# Hexagon_Robot1.net
KiCad netlist of a schematic drawn in EasyEDA
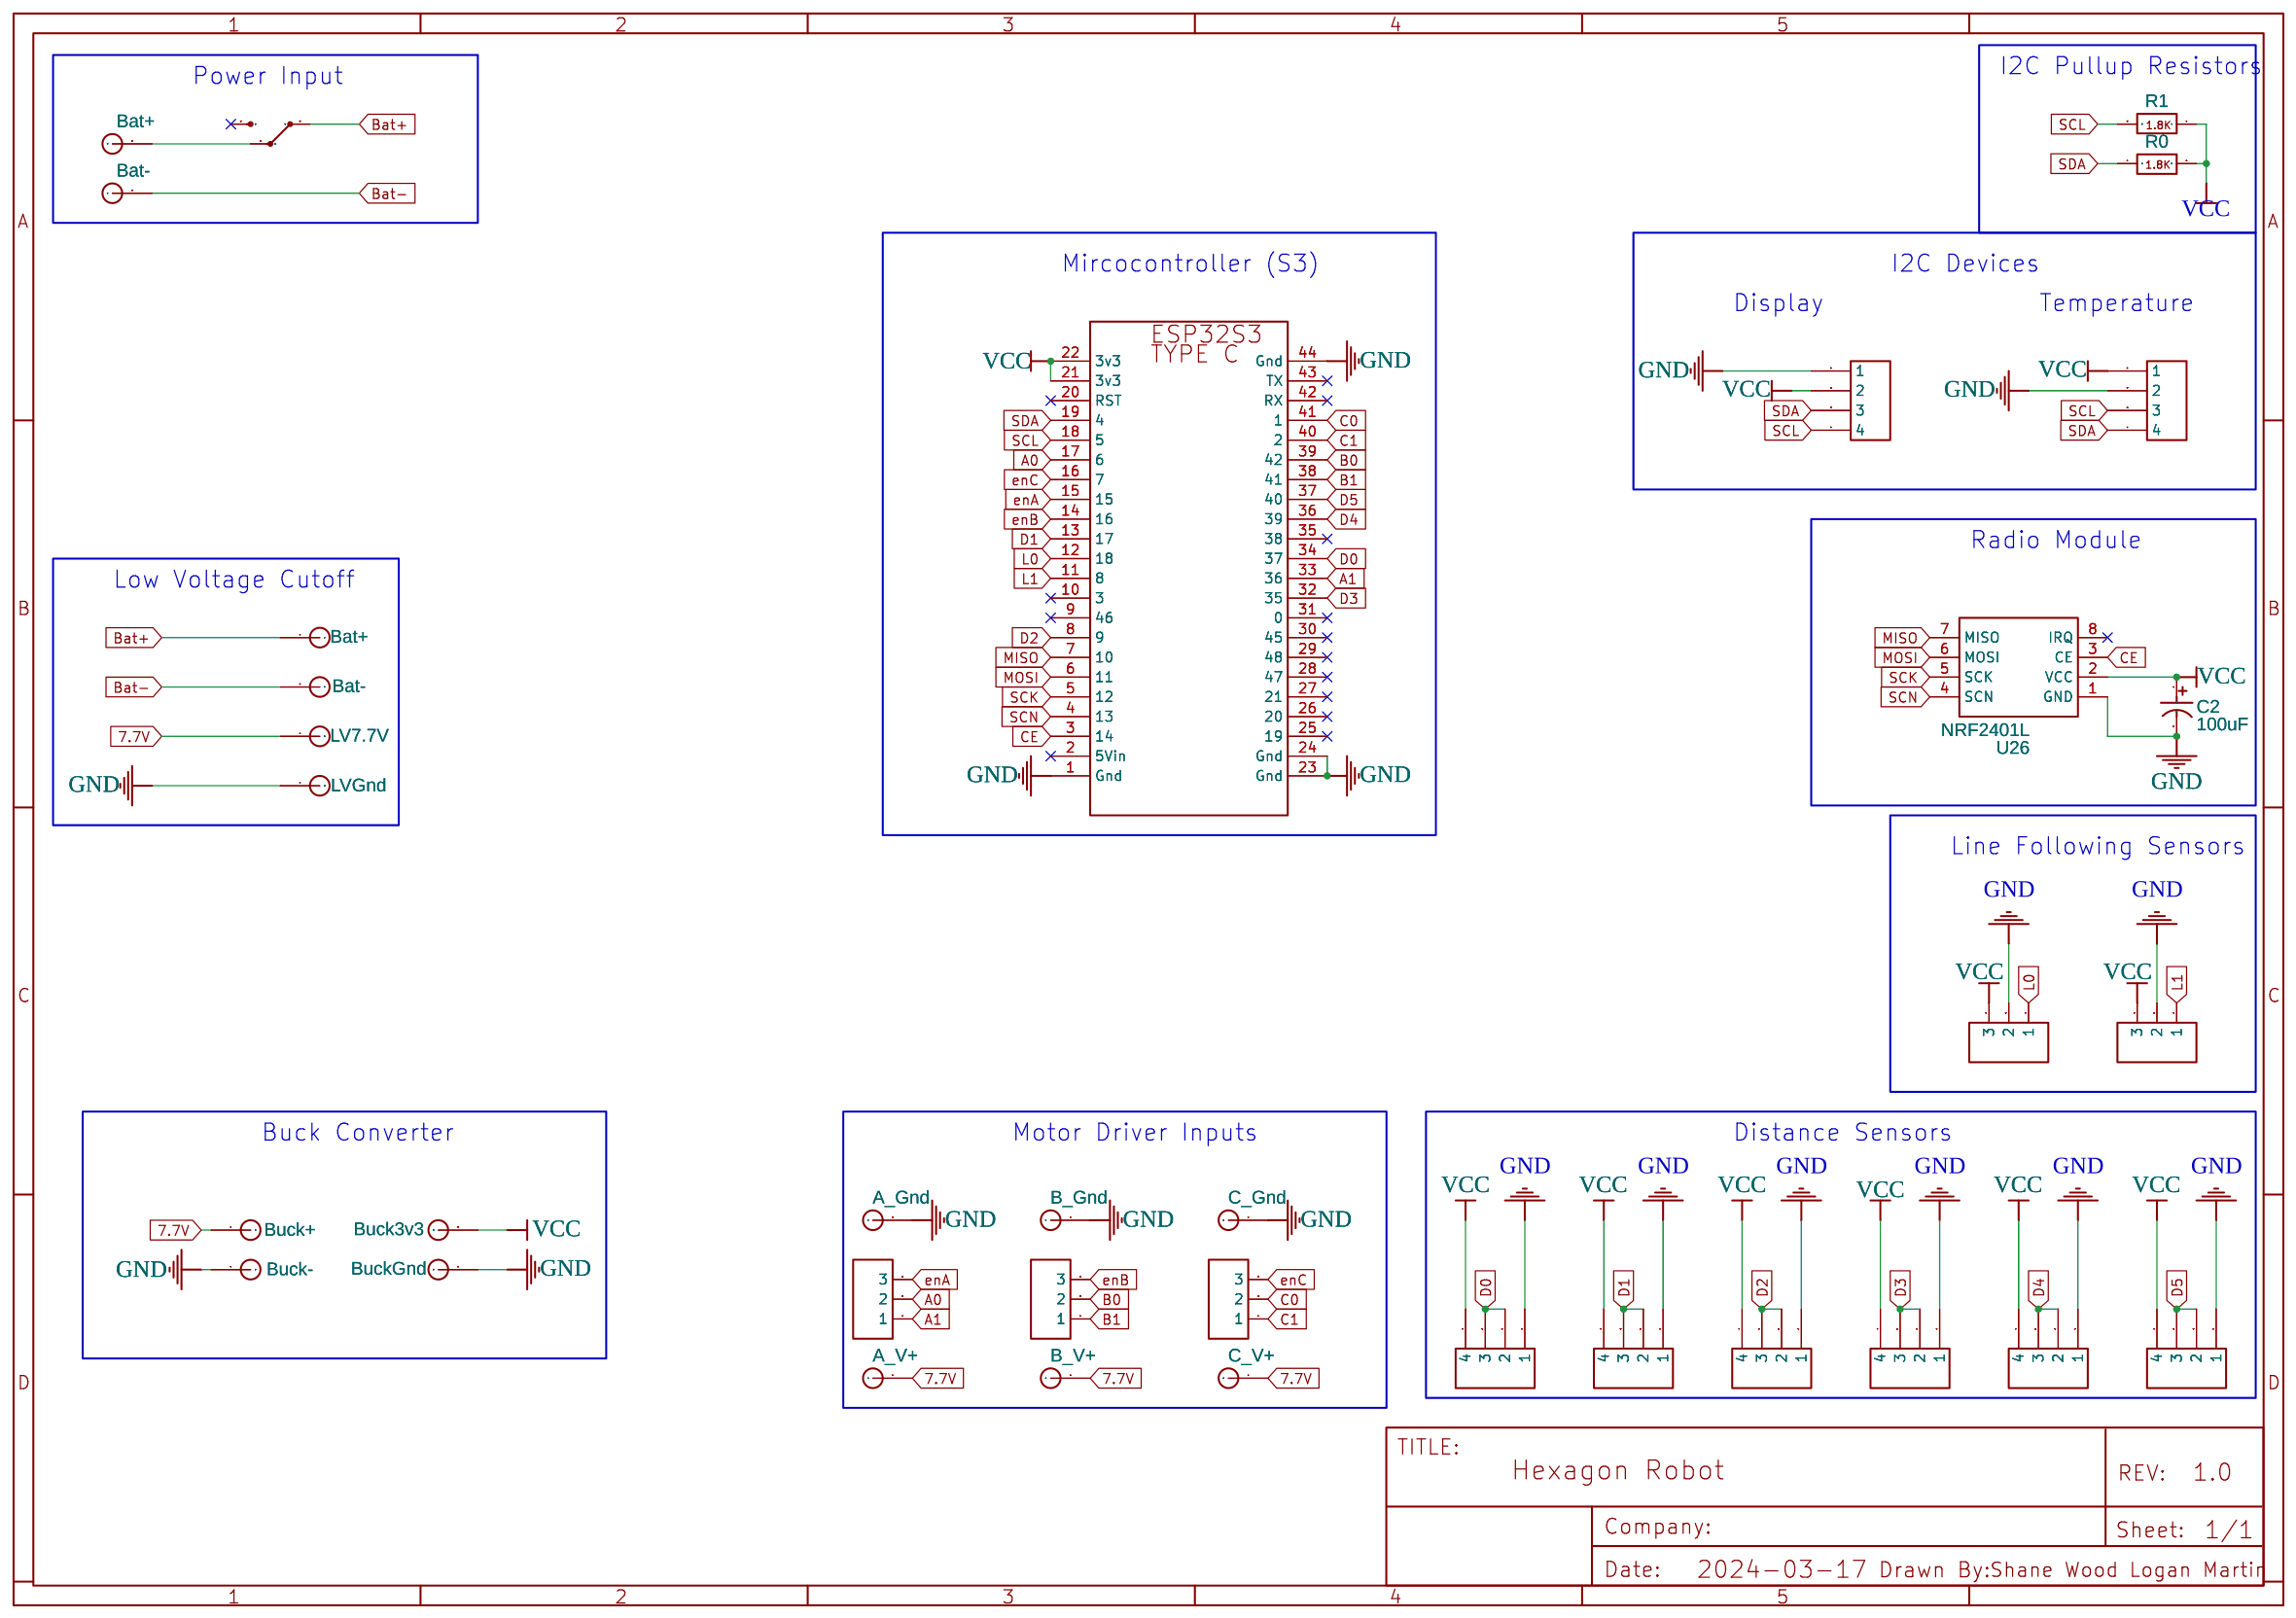
[diagram p0: schematic sheet]

(export (version "E")
  (design (tool "Eeschema 10.0.6"))
  (components
    (comp (ref "C2")
      (value "100uF")
      (fields (field (name "Manufacturer Part") "Jweo"))
      (libsource (lib "") (part "CAP-POL-1"))
    )
    (comp (ref "H1")
      (value "Bat+")
      (fields (field (name "Manufacturer Part") "Wire Hole"))
      (libsource (lib "") (part "Wire Hole 14AWG_1"))
    )
    (comp (ref "H2")
      (value "Bat-")
      (fields (field (name "Manufacturer Part") "Wire Hole"))
      (libsource (lib "") (part "Wire Hole 14AWG_1"))
    )
    (comp (ref "H3")
      (value "Bat+")
      (fields (field (name "Manufacturer Part") "Wire Hole"))
      (libsource (lib "") (part "Wire Hole 14AWG"))
    )
    (comp (ref "H4")
      (value "LVGnd")
      (fields (field (name "Manufacturer Part") "Wire Hole"))
      (libsource (lib "") (part "Wire Hole 14AWG"))
    )
    (comp (ref "H5")
      (value "Bat-")
      (fields (field (name "Manufacturer Part") "Wire Hole"))
      (libsource (lib "") (part "Wire Hole 14AWG"))
    )
    (comp (ref "H6")
      (value "LV7.7V")
      (fields (field (name "Manufacturer Part") "Wire Hole"))
      (libsource (lib "") (part "Wire Hole 14AWG"))
    )
    (comp (ref "H11")
      (value "A_Gnd")
      (fields (field (name "Manufacturer Part") "Wire Hole"))
      (libsource (lib "") (part "Wire Hole 14AWG_1"))
    )
    (comp (ref "H12")
      (value "B_Gnd")
      (fields (field (name "Manufacturer Part") "Wire Hole"))
      (libsource (lib "") (part "Wire Hole 14AWG_1"))
    )
    (comp (ref "H13")
      (value "C_Gnd")
      (fields (field (name "Manufacturer Part") "Wire Hole"))
      (libsource (lib "") (part "Wire Hole 14AWG_1"))
    )
    (comp (ref "H14")
      (value "A_V+")
      (fields (field (name "Manufacturer Part") "Wire Hole"))
      (libsource (lib "") (part "Wire Hole 14AWG_1"))
    )
    (comp (ref "H15")
      (value "B_V+")
      (fields (field (name "Manufacturer Part") "Wire Hole"))
      (libsource (lib "") (part "Wire Hole 14AWG_1"))
    )
    (comp (ref "H16")
      (value "C_V+")
      (fields (field (name "Manufacturer Part") "Wire Hole"))
      (libsource (lib "") (part "Wire Hole 14AWG_1"))
    )
    (comp (ref "H17")
      (value "Buck+")
      (fields (field (name "Manufacturer Part") "Wire Hole"))
      (libsource (lib "") (part "Wire Hole 14AWG"))
    )
    (comp (ref "H18")
      (value "Buck-")
      (fields (field (name "Manufacturer Part") "Wire Hole"))
      (libsource (lib "") (part "Wire Hole 14AWG"))
    )
    (comp (ref "H19")
      (value "Buck3v3")
      (fields (field (name "Manufacturer Part") "Wire Hole"))
      (libsource (lib "") (part "Wire Hole 14AWG_1"))
    )
    (comp (ref "H20")
      (value "BuckGnd")
      (fields (field (name "Manufacturer Part") "Wire Hole"))
      (libsource (lib "") (part "Wire Hole 14AWG_1"))
    )
    (comp (ref "P9")
      (value "Header-Female-2.54_1x3")
      (fields
        (field (name "Manufacturer Part") "Header-Female-2.54_1x4")
        (field (name "Manufacturer") "ReliaPro")
      )
      (libsource (lib "") (part "Header-Female-2.54_1x3_1"))
    )
    (comp (ref "P10")
      (value "Header-Female-2.54_1x3")
      (fields
        (field (name "Manufacturer Part") "Header-Female-2.54_1x4")
        (field (name "Manufacturer") "ReliaPro")
      )
      (libsource (lib "") (part "Header-Female-2.54_1x3_1"))
    )
    (comp (ref "P11")
      (value "Header-Female-2.54_1x3")
      (fields
        (field (name "Manufacturer Part") "Header-Female-2.54_1x4")
        (field (name "Manufacturer") "ReliaPro")
      )
      (libsource (lib "") (part "Header-Female-2.54_1x3"))
    )
    (comp (ref "P12")
      (value "Header-Female-2.54_1x3")
      (fields
        (field (name "Manufacturer Part") "Header-Female-2.54_1x4")
        (field (name "Manufacturer") "ReliaPro")
      )
      (libsource (lib "") (part "Header-Female-2.54_1x3"))
    )
    (comp (ref "P13")
      (value "Header-Female-2.54_1x3")
      (fields
        (field (name "Manufacturer Part") "Header-Female-2.54_1x4")
        (field (name "Manufacturer") "ReliaPro")
      )
      (libsource (lib "") (part "Header-Female-2.54_1x3"))
    )
    (comp (ref "R3") (value "R1") (libsource (lib "") (part "1.8K_R_1/2W")))
    (comp (ref "R4") (value "R0") (libsource (lib "") (part "1.8K_R_1/2W_1")))
    (comp (ref "U2")
      (value "NO")
      (fields
        (field (name "Manufacturer Part") "Female header pitch2.54mm")
        (field (name "Manufacturer") "ReliaPro")
      )
      (libsource (lib "") (part "Header-Female-2.54_1x4_1"))
    )
    (comp (ref "U3") (value "ESP32S3 TypeC") (libsource (lib "") (part "ESP32S3 TypeC")))
    (comp (ref "U22") (value "NO") (libsource (lib "") (part "TOGGLESWITCH SPST_SWITCH-SPDT COPY")))
    (comp (ref "U26")
      (value "NRF2401L")
      (fields (field (name "Manufacturer Part") "nrf2401l"))
      (libsource (lib "") (part "NRF2401L"))
    )
    (comp (ref "U28")
      (value "NO")
      (fields
        (field (name "Manufacturer Part") "Female header pitch2.54mm")
        (field (name "Manufacturer") "ReliaPro")
      )
      (libsource (lib "") (part "Header-Female-2.54_1x4"))
    )
    (comp (ref "U29")
      (value "NO")
      (fields
        (field (name "Manufacturer Part") "Female header pitch2.54mm")
        (field (name "Manufacturer") "ReliaPro")
      )
      (libsource (lib "") (part "Header-Female-2.54_1x4"))
    )
    (comp (ref "U30")
      (value "NO")
      (fields
        (field (name "Manufacturer Part") "Female header pitch2.54mm")
        (field (name "Manufacturer") "ReliaPro")
      )
      (libsource (lib "") (part "Header-Female-2.54_1x4"))
    )
    (comp (ref "U31")
      (value "NO")
      (fields
        (field (name "Manufacturer Part") "Female header pitch2.54mm")
        (field (name "Manufacturer") "ReliaPro")
      )
      (libsource (lib "") (part "Header-Female-2.54_1x4"))
    )
    (comp (ref "U32")
      (value "NO")
      (fields
        (field (name "Manufacturer Part") "Female header pitch2.54mm")
        (field (name "Manufacturer") "ReliaPro")
      )
      (libsource (lib "") (part "Header-Female-2.54_1x4"))
    )
    (comp (ref "U33")
      (value "NO")
      (fields
        (field (name "Manufacturer Part") "Female header pitch2.54mm")
        (field (name "Manufacturer") "ReliaPro")
      )
      (libsource (lib "") (part "Header-Female-2.54_1x4"))
    )
    (comp (ref "U35")
      (value "NO")
      (fields
        (field (name "Manufacturer Part") "Female header pitch2.54mm")
        (field (name "Manufacturer") "ReliaPro")
      )
      (libsource (lib "") (part "Header-Female-2.54_1x4_1"))
    )
  )
  (nets
    (net (code "1") (name "7.7V") (class "Default")
      (node (ref "H14") (pin "1") (pinfunction "1_1") (pintype "unspecified"))
      (node (ref "H15") (pin "1") (pinfunction "1_1") (pintype "unspecified"))
      (node (ref "H16") (pin "1") (pinfunction "1_1") (pintype "unspecified"))
      (node (ref "H17") (pin "1") (pinfunction "1_1") (pintype "unspecified"))
      (node (ref "H6") (pin "1") (pinfunction "1_1") (pintype "unspecified"))
    )
    (net (code "2") (name "A0") (class "Default")
      (node (ref "P11") (pin "2") (pinfunction "2_2") (pintype "input"))
      (node (ref "U3") (pin "17") (pinfunction "6_17") (pintype "unspecified"))
    )
    (net (code "3") (name "A1") (class "Default")
      (node (ref "P11") (pin "1") (pinfunction "1_1") (pintype "input"))
      (node (ref "U3") (pin "33") (pinfunction "36_33") (pintype "unspecified"))
    )
    (net (code "4") (name "B0") (class "Default")
      (node (ref "P12") (pin "2") (pinfunction "2_2") (pintype "input"))
      (node (ref "U3") (pin "39") (pinfunction "42_39") (pintype "unspecified"))
    )
    (net (code "5") (name "B1") (class "Default")
      (node (ref "P12") (pin "1") (pinfunction "1_1") (pintype "input"))
      (node (ref "U3") (pin "38") (pinfunction "41_38") (pintype "unspecified"))
    )
    (net (code "6") (name "Bat+") (class "Default")
      (node (ref "H3") (pin "1") (pinfunction "1_1") (pintype "unspecified"))
      (node (ref "U22") (pin "2") (pinfunction "P_2") (pintype "unspecified"))
    )
    (net (code "7") (name "Bat-") (class "Default")
      (node (ref "H2") (pin "1") (pinfunction "1_1") (pintype "unspecified"))
      (node (ref "H5") (pin "1") (pinfunction "1_1") (pintype "unspecified"))
    )
    (net (code "8") (name "C0") (class "Default")
      (node (ref "P13") (pin "2") (pinfunction "2_2") (pintype "input"))
      (node (ref "U3") (pin "41") (pinfunction "1_41") (pintype "unspecified"))
    )
    (net (code "9") (name "C1") (class "Default")
      (node (ref "P13") (pin "1") (pinfunction "1_1") (pintype "input"))
      (node (ref "U3") (pin "40") (pinfunction "2_40") (pintype "unspecified"))
    )
    (net (code "10") (name "CE") (class "Default")
      (node (ref "U26") (pin "3") (pinfunction "CE_3") (pintype "unspecified"))
      (node (ref "U3") (pin "3") (pinfunction "14_3") (pintype "unspecified"))
    )
    (net (code "11") (name "D0") (class "Default")
      (node (ref "U28") (pin "2") (pinfunction "2_2") (pintype "input"))
      (node (ref "U28") (pin "3") (pinfunction "3_3") (pintype "input"))
      (node (ref "U3") (pin "34") (pinfunction "37_34") (pintype "unspecified"))
    )
    (net (code "12") (name "D1") (class "Default")
      (node (ref "U29") (pin "2") (pinfunction "2_2") (pintype "input"))
      (node (ref "U29") (pin "3") (pinfunction "3_3") (pintype "input"))
      (node (ref "U3") (pin "13") (pinfunction "17_13") (pintype "unspecified"))
    )
    (net (code "13") (name "D2") (class "Default")
      (node (ref "U3") (pin "8") (pinfunction "9_8") (pintype "unspecified"))
      (node (ref "U30") (pin "2") (pinfunction "2_2") (pintype "input"))
      (node (ref "U30") (pin "3") (pinfunction "3_3") (pintype "input"))
    )
    (net (code "14") (name "D3") (class "Default")
      (node (ref "U3") (pin "32") (pinfunction "35_32") (pintype "unspecified"))
      (node (ref "U31") (pin "2") (pinfunction "2_2") (pintype "input"))
      (node (ref "U31") (pin "3") (pinfunction "3_3") (pintype "input"))
    )
    (net (code "15") (name "D4") (class "Default")
      (node (ref "U3") (pin "36") (pinfunction "39_36") (pintype "unspecified"))
      (node (ref "U32") (pin "2") (pinfunction "2_2") (pintype "input"))
      (node (ref "U32") (pin "3") (pinfunction "3_3") (pintype "input"))
    )
    (net (code "16") (name "D5") (class "Default")
      (node (ref "U3") (pin "37") (pinfunction "40_37") (pintype "unspecified"))
      (node (ref "U33") (pin "2") (pinfunction "2_2") (pintype "input"))
      (node (ref "U33") (pin "3") (pinfunction "3_3") (pintype "input"))
    )
    (net (code "17") (name "GND") (class "Default")
      (node (ref "C2") (pin "2") (pinfunction "2_2") (pintype "input"))
      (node (ref "H11") (pin "1") (pinfunction "1_1") (pintype "unspecified"))
      (node (ref "H12") (pin "1") (pinfunction "1_1") (pintype "unspecified"))
      (node (ref "H13") (pin "1") (pinfunction "1_1") (pintype "unspecified"))
      (node (ref "H18") (pin "1") (pinfunction "1_1") (pintype "unspecified"))
      (node (ref "H20") (pin "1") (pinfunction "1_1") (pintype "unspecified"))
      (node (ref "H4") (pin "1") (pinfunction "1_1") (pintype "unspecified"))
      (node (ref "P10") (pin "2") (pinfunction "2_2") (pintype "input"))
      (node (ref "P9") (pin "2") (pinfunction "2_2") (pintype "input"))
      (node (ref "U2") (pin "1") (pinfunction "1_1") (pintype "input"))
      (node (ref "U26") (pin "1") (pinfunction "GND_1") (pintype "unspecified"))
      (node (ref "U28") (pin "1") (pinfunction "1_1") (pintype "input"))
      (node (ref "U29") (pin "1") (pinfunction "1_1") (pintype "input"))
      (node (ref "U3") (pin "1") (pinfunction "Gnd_1") (pintype "unspecified"))
      (node (ref "U3") (pin "23") (pinfunction "Gnd_23") (pintype "unspecified"))
      (node (ref "U3") (pin "24") (pinfunction "Gnd_24") (pintype "unspecified"))
      (node (ref "U3") (pin "44") (pinfunction "Gnd_44") (pintype "unspecified"))
      (node (ref "U30") (pin "1") (pinfunction "1_1") (pintype "input"))
      (node (ref "U31") (pin "1") (pinfunction "1_1") (pintype "input"))
      (node (ref "U32") (pin "1") (pinfunction "1_1") (pintype "input"))
      (node (ref "U33") (pin "1") (pinfunction "1_1") (pintype "input"))
      (node (ref "U35") (pin "2") (pinfunction "2_2") (pintype "input"))
    )
    (net (code "18") (name "L0") (class "Default")
      (node (ref "P9") (pin "1") (pinfunction "1_1") (pintype "input"))
      (node (ref "U3") (pin "12") (pinfunction "18_12") (pintype "unspecified"))
    )
    (net (code "19") (name "L1") (class "Default")
      (node (ref "P10") (pin "1") (pinfunction "1_1") (pintype "input"))
      (node (ref "U3") (pin "11") (pinfunction "8_11") (pintype "unspecified"))
    )
    (net (code "20") (name "MISO") (class "Default")
      (node (ref "U26") (pin "7") (pinfunction "MISO_7") (pintype "unspecified"))
      (node (ref "U3") (pin "7") (pinfunction "10_7") (pintype "unspecified"))
    )
    (net (code "21") (name "MOSI") (class "Default")
      (node (ref "U26") (pin "6") (pinfunction "MOSI_6") (pintype "unspecified"))
      (node (ref "U3") (pin "6") (pinfunction "11_6") (pintype "unspecified"))
    )
    (net (code "22") (name "Net-(U22-O)") (class "Default")
      (node (ref "H1") (pin "1") (pinfunction "1_1") (pintype "unspecified"))
      (node (ref "U22") (pin "1") (pinfunction "O_1") (pintype "unspecified"))
    )
    (net (code "23") (name "SCK") (class "Default")
      (node (ref "U26") (pin "5") (pinfunction "SCK_5") (pintype "unspecified"))
      (node (ref "U3") (pin "5") (pinfunction "12_5") (pintype "unspecified"))
    )
    (net (code "24") (name "SCL") (class "Default")
      (node (ref "R3") (pin "2") (pinfunction "2_2") (pintype "unspecified"))
      (node (ref "U2") (pin "4") (pinfunction "4_4") (pintype "input"))
      (node (ref "U3") (pin "18") (pinfunction "5_18") (pintype "unspecified"))
      (node (ref "U35") (pin "3") (pinfunction "3_3") (pintype "input"))
    )
    (net (code "25") (name "SCN") (class "Default")
      (node (ref "U26") (pin "4") (pinfunction "SCN_4") (pintype "unspecified"))
      (node (ref "U3") (pin "4") (pinfunction "13_4") (pintype "unspecified"))
    )
    (net (code "26") (name "SDA") (class "Default")
      (node (ref "R4") (pin "1") (pinfunction "1_1") (pintype "unspecified"))
      (node (ref "U2") (pin "3") (pinfunction "3_3") (pintype "input"))
      (node (ref "U3") (pin "19") (pinfunction "4_19") (pintype "unspecified"))
      (node (ref "U35") (pin "4") (pinfunction "4_4") (pintype "input"))
    )
    (net (code "27") (name "VCC") (class "Default")
      (node (ref "C2") (pin "1") (pinfunction "1_1") (pintype "input"))
      (node (ref "H19") (pin "1") (pinfunction "1_1") (pintype "unspecified"))
      (node (ref "P10") (pin "3") (pinfunction "3_3") (pintype "input"))
      (node (ref "P9") (pin "3") (pinfunction "3_3") (pintype "input"))
      (node (ref "R3") (pin "1") (pinfunction "1_1") (pintype "unspecified"))
      (node (ref "R4") (pin "2") (pinfunction "2_2") (pintype "unspecified"))
      (node (ref "U2") (pin "2") (pinfunction "2_2") (pintype "input"))
      (node (ref "U26") (pin "2") (pinfunction "VCC_2") (pintype "unspecified"))
      (node (ref "U28") (pin "4") (pinfunction "4_4") (pintype "input"))
      (node (ref "U29") (pin "4") (pinfunction "4_4") (pintype "input"))
      (node (ref "U3") (pin "21") (pinfunction "3v3_21") (pintype "unspecified"))
      (node (ref "U3") (pin "22") (pinfunction "3v3_22") (pintype "unspecified"))
      (node (ref "U30") (pin "4") (pinfunction "4_4") (pintype "input"))
      (node (ref "U31") (pin "4") (pinfunction "4_4") (pintype "input"))
      (node (ref "U32") (pin "4") (pinfunction "4_4") (pintype "input"))
      (node (ref "U33") (pin "4") (pinfunction "4_4") (pintype "input"))
      (node (ref "U35") (pin "1") (pinfunction "1_1") (pintype "input"))
    )
    (net (code "28") (name "enA") (class "Default")
      (node (ref "P11") (pin "3") (pinfunction "3_3") (pintype "input"))
      (node (ref "U3") (pin "15") (pinfunction "15_15") (pintype "unspecified"))
    )
    (net (code "29") (name "enB") (class "Default")
      (node (ref "P12") (pin "3") (pinfunction "3_3") (pintype "input"))
      (node (ref "U3") (pin "14") (pinfunction "16_14") (pintype "unspecified"))
    )
    (net (code "30") (name "enC") (class "Default")
      (node (ref "P13") (pin "3") (pinfunction "3_3") (pintype "input"))
      (node (ref "U3") (pin "16") (pinfunction "7_16") (pintype "unspecified"))
    )
    (net (code "31") (name "unconnected-(U3-0-Pad31)") (class "Default")
      (node (ref "U3") (pin "31") (pinfunction "0_31") (pintype "unspecified+no_connect"))
    )
    (net (code "32") (name "unconnected-(U3-3-Pad10)") (class "Default")
      (node (ref "U3") (pin "10") (pinfunction "3_10") (pintype "unspecified+no_connect"))
    )
    (net (code "33") (name "unconnected-(U3-5Vin-Pad2)") (class "Default")
      (node (ref "U3") (pin "2") (pinfunction "5Vin_2") (pintype "unspecified+no_connect"))
    )
    (net (code "34") (name "unconnected-(U3-19-Pad25)") (class "Default")
      (node (ref "U3") (pin "25") (pinfunction "19_25") (pintype "unspecified+no_connect"))
    )
    (net (code "35") (name "unconnected-(U3-20-Pad26)") (class "Default")
      (node (ref "U3") (pin "26") (pinfunction "20_26") (pintype "unspecified+no_connect"))
    )
    (net (code "36") (name "unconnected-(U3-21-Pad27)") (class "Default")
      (node (ref "U3") (pin "27") (pinfunction "21_27") (pintype "unspecified+no_connect"))
    )
    (net (code "37") (name "unconnected-(U3-38-Pad35)") (class "Default")
      (node (ref "U3") (pin "35") (pinfunction "38_35") (pintype "unspecified+no_connect"))
    )
    (net (code "38") (name "unconnected-(U3-45-Pad30)") (class "Default")
      (node (ref "U3") (pin "30") (pinfunction "45_30") (pintype "unspecified+no_connect"))
    )
    (net (code "39") (name "unconnected-(U3-46-Pad9)") (class "Default")
      (node (ref "U3") (pin "9") (pinfunction "46_9") (pintype "unspecified+no_connect"))
    )
    (net (code "40") (name "unconnected-(U3-47-Pad28)") (class "Default")
      (node (ref "U3") (pin "28") (pinfunction "47_28") (pintype "unspecified+no_connect"))
    )
    (net (code "41") (name "unconnected-(U3-48-Pad29)") (class "Default")
      (node (ref "U3") (pin "29") (pinfunction "48_29") (pintype "unspecified+no_connect"))
    )
    (net (code "42") (name "unconnected-(U3-RST-Pad20)") (class "Default")
      (node (ref "U3") (pin "20") (pinfunction "RST_20") (pintype "unspecified+no_connect"))
    )
    (net (code "43") (name "unconnected-(U3-RX-Pad42)") (class "Default")
      (node (ref "U3") (pin "42") (pinfunction "RX_42") (pintype "unspecified+no_connect"))
    )
    (net (code "44") (name "unconnected-(U3-TX-Pad43)") (class "Default")
      (node (ref "U3") (pin "43") (pinfunction "TX_43") (pintype "unspecified+no_connect"))
    )
    (net (code "45") (name "unconnected-(U22-S-Pad3)") (class "Default")
      (node (ref "U22") (pin "3") (pinfunction "S_3") (pintype "unspecified+no_connect"))
    )
    (net (code "46") (name "unconnected-(U26-IRQ-Pad8)") (class "Default")
      (node (ref "U26") (pin "8") (pinfunction "IRQ_8") (pintype "unspecified+no_connect"))
    )
  )
)
